# sputnik_prototype.net
KiCad netlist of a schematic drawn in EAGLE
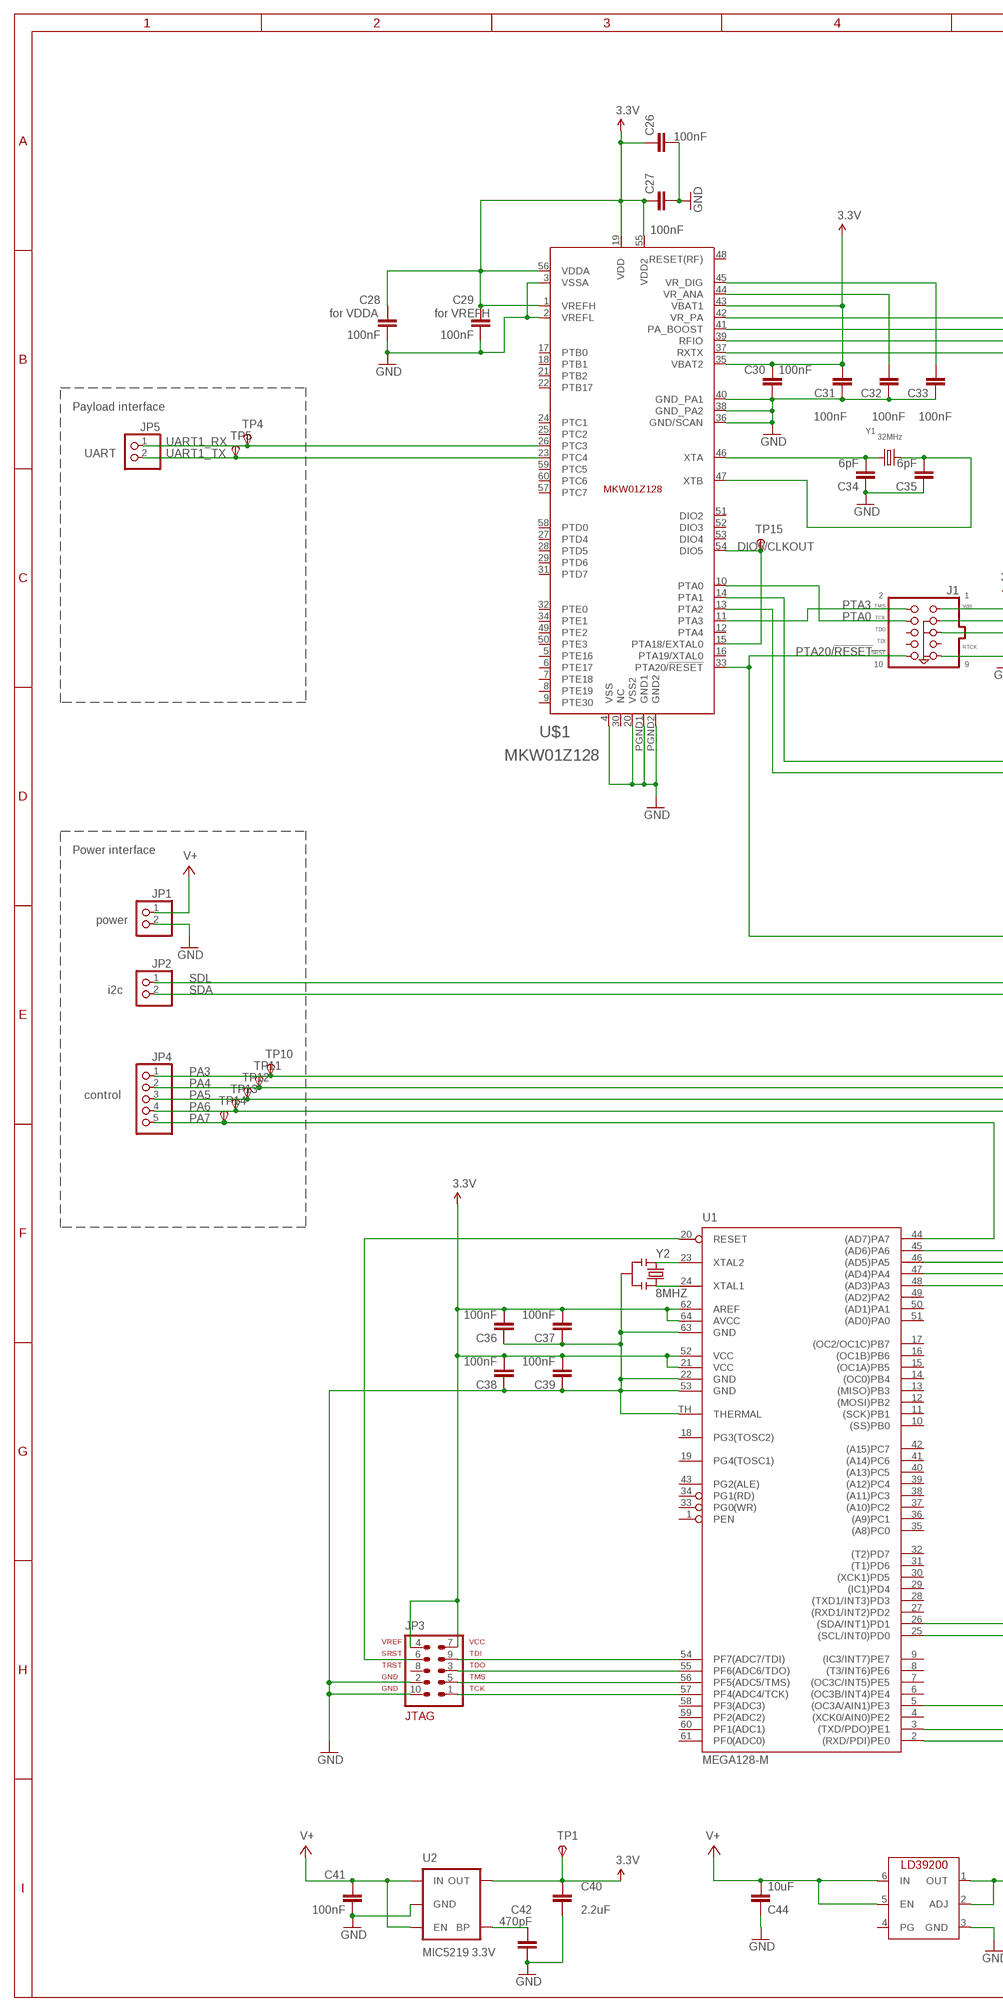
[diagram p0: schematic, sheet 1, part 1 of 2]
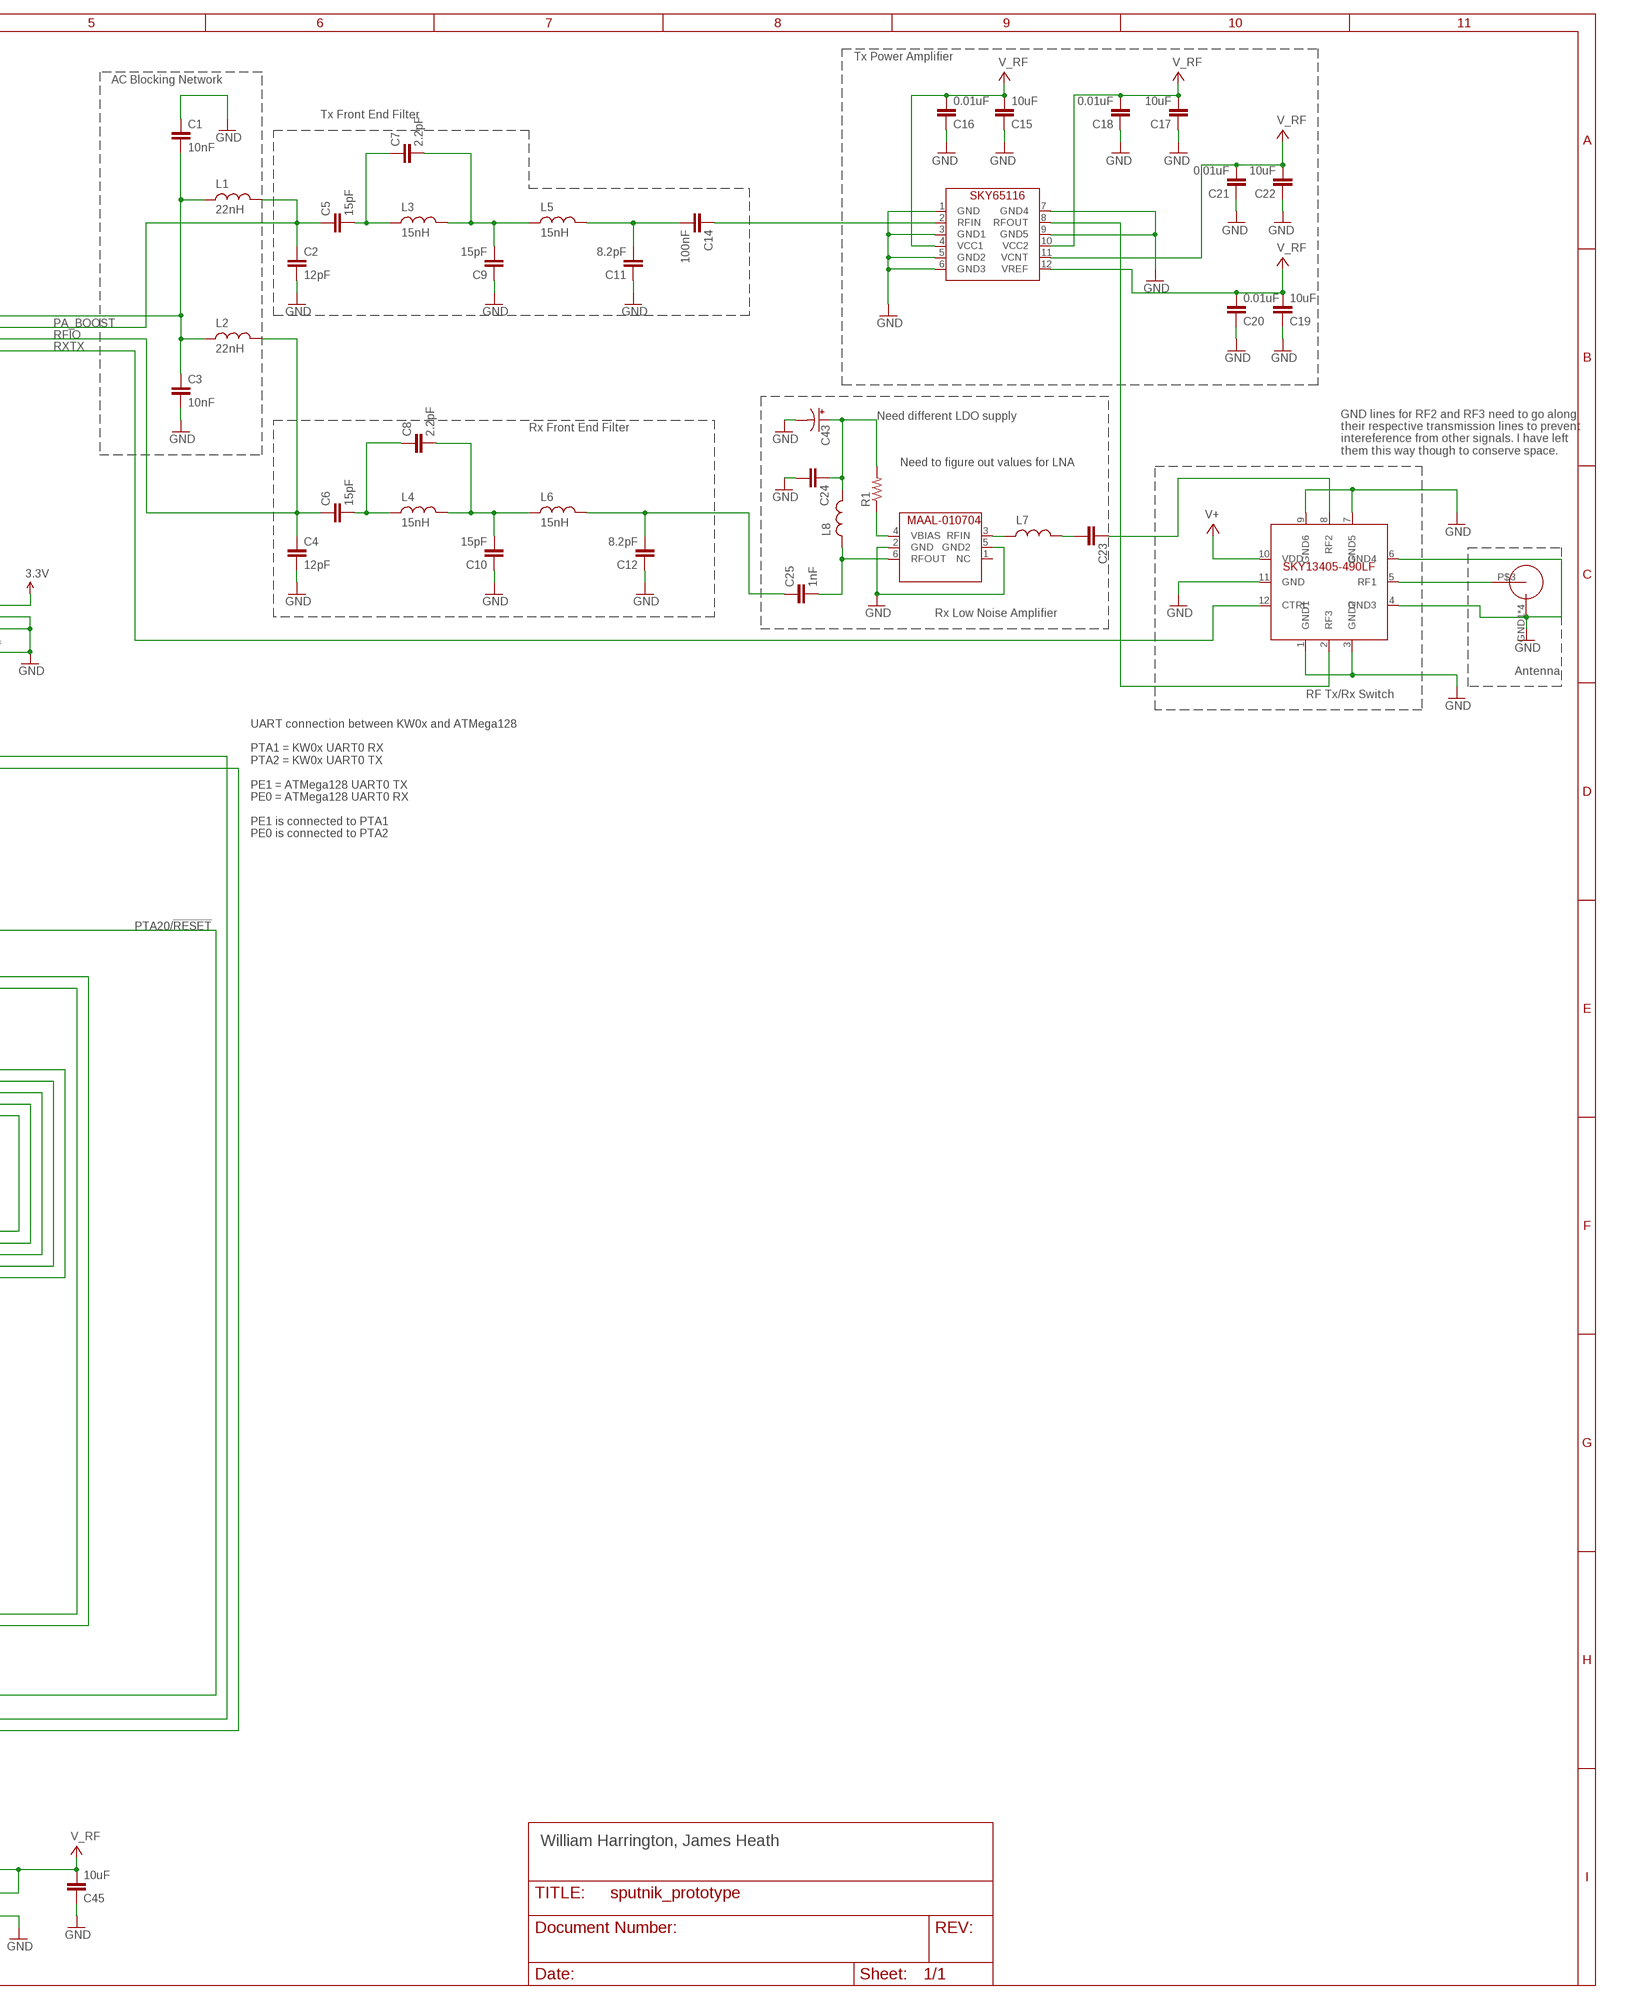
[diagram p1: schematic, sheet 1, part 2 of 2]

(export (version "E")
  (design (tool "Eeschema 10.0.6"))
  (components
    (comp (ref "C1")
      (value "10nF")
      (footprint "eagle-import:.0603-B-NOSILK")
      (libsource (lib "eagle-import") (part "C-EU0603-B-NOSILK"))
    )
    (comp (ref "C2")
      (value "12pF")
      (footprint "eagle-import:.0603-B-NOSILK")
      (libsource (lib "eagle-import") (part "C-EU0603-B-NOSILK"))
    )
    (comp (ref "C3")
      (value "10nF")
      (footprint "eagle-import:.0603-B-NOSILK")
      (libsource (lib "eagle-import") (part "C-EU0603-B-NOSILK"))
    )
    (comp (ref "C4")
      (value "12pF")
      (footprint "eagle-import:.0603-B-NOSILK")
      (libsource (lib "eagle-import") (part "C-EU0603-B-NOSILK"))
    )
    (comp (ref "C5")
      (value "15pF")
      (footprint "eagle-import:.0603-B-NOSILK")
      (libsource (lib "eagle-import") (part "C-EU0603-B-NOSILK"))
    )
    (comp (ref "C6")
      (value "15pF")
      (footprint "eagle-import:.0603-B-NOSILK")
      (libsource (lib "eagle-import") (part "C-EU0603-B-NOSILK"))
    )
    (comp (ref "C7")
      (value "2.2pF")
      (footprint "eagle-import:.0603-B-NOSILK")
      (libsource (lib "eagle-import") (part "C-EU0603-B-NOSILK"))
    )
    (comp (ref "C8")
      (value "2.2pF")
      (footprint "eagle-import:.0603-B-NOSILK")
      (libsource (lib "eagle-import") (part "C-EU0603-B-NOSILK"))
    )
    (comp (ref "C9")
      (value "15pF")
      (footprint "eagle-import:.0603-B-NOSILK")
      (libsource (lib "eagle-import") (part "C-EU0603-B-NOSILK"))
    )
    (comp (ref "C10")
      (value "15pF")
      (footprint "eagle-import:.0603-B-NOSILK")
      (libsource (lib "eagle-import") (part "C-EU0603-B-NOSILK"))
    )
    (comp (ref "C11")
      (value "8.2pF")
      (footprint "eagle-import:.0603-B-NOSILK")
      (libsource (lib "eagle-import") (part "C-EU0603-B-NOSILK"))
    )
    (comp (ref "C12")
      (value "8.2pF")
      (footprint "eagle-import:.0603-B-NOSILK")
      (libsource (lib "eagle-import") (part "C-EU0603-B-NOSILK"))
    )
    (comp (ref "C14")
      (value "100nF")
      (footprint "eagle-import:.0603-B-NOSILK")
      (libsource (lib "eagle-import") (part "C-EU0603-B-NOSILK"))
    )
    (comp (ref "C15")
      (value "10uF")
      (footprint "eagle-import:.0603-B-NOSILK")
      (libsource (lib "eagle-import") (part "C-EU0603-B-NOSILK"))
    )
    (comp (ref "C16")
      (value "0.01uF")
      (footprint "eagle-import:.0603-B-NOSILK")
      (libsource (lib "eagle-import") (part "C-EU0603-B-NOSILK"))
    )
    (comp (ref "C17")
      (value "10uF")
      (footprint "eagle-import:.0603-B-NOSILK")
      (libsource (lib "eagle-import") (part "C-EU0603-B-NOSILK"))
    )
    (comp (ref "C18")
      (value "0.01uF")
      (footprint "eagle-import:.0603-B-NOSILK")
      (libsource (lib "eagle-import") (part "C-EU0603-B-NOSILK"))
    )
    (comp (ref "C19")
      (value "10uF")
      (footprint "eagle-import:.0603-B-NOSILK")
      (libsource (lib "eagle-import") (part "C-EU0603-B-NOSILK"))
    )
    (comp (ref "C20")
      (value "0.01uF")
      (footprint "eagle-import:.0603-B-NOSILK")
      (libsource (lib "eagle-import") (part "C-EU0603-B-NOSILK"))
    )
    (comp (ref "C21")
      (value "0.01uF")
      (footprint "eagle-import:.0603-B-NOSILK")
      (libsource (lib "eagle-import") (part "C-EU0603-B-NOSILK"))
    )
    (comp (ref "C22")
      (value "10uF")
      (footprint "eagle-import:.0603-B-NOSILK")
      (libsource (lib "eagle-import") (part "C-EU0603-B-NOSILK"))
    )
    (comp (ref "C23")
      (value "C-EU0402-B-NOSILK")
      (footprint "eagle-import:.0402-B-NOSILK")
      (libsource (lib "eagle-import") (part "C-EU0402-B-NOSILK"))
    )
    (comp (ref "C24")
      (value "C-EU0402-B-NOSILK")
      (footprint "eagle-import:.0402-B-NOSILK")
      (libsource (lib "eagle-import") (part "C-EU0402-B-NOSILK"))
    )
    (comp (ref "C25")
      (value "1nF")
      (footprint "eagle-import:.0402-B-NOSILK")
      (libsource (lib "eagle-import") (part "C-EU0402-B-NOSILK"))
    )
    (comp (ref "C26")
      (value "100nF")
      (footprint "eagle-import:.0603-B-NOSILK")
      (libsource (lib "eagle-import") (part "C-EU0603-B-NOSILK"))
    )
    (comp (ref "C27")
      (value "100nF")
      (footprint "eagle-import:.0603-B-NOSILK")
      (libsource (lib "eagle-import") (part "C-EU0603-B-NOSILK"))
    )
    (comp (ref "C28")
      (value "100nF")
      (footprint "eagle-import:.0603-B-NOSILK")
      (libsource (lib "eagle-import") (part "C-EU0603-B-NOSILK"))
    )
    (comp (ref "C29")
      (value "100nF")
      (footprint "eagle-import:.0603-B-NOSILK")
      (libsource (lib "eagle-import") (part "C-EU0603-B-NOSILK"))
    )
    (comp (ref "C30")
      (value "100nF")
      (footprint "eagle-import:.0603-B-NOSILK")
      (libsource (lib "eagle-import") (part "C-EU0603-B-NOSILK"))
    )
    (comp (ref "C31")
      (value "100nF")
      (footprint "eagle-import:.0603-B-NOSILK")
      (libsource (lib "eagle-import") (part "C-EU0603-B-NOSILK"))
    )
    (comp (ref "C32")
      (value "100nF")
      (footprint "eagle-import:.0603-B-NOSILK")
      (libsource (lib "eagle-import") (part "C-EU0603-B-NOSILK"))
    )
    (comp (ref "C33")
      (value "100nF")
      (footprint "eagle-import:.0603-B-NOSILK")
      (libsource (lib "eagle-import") (part "C-EU0603-B-NOSILK"))
    )
    (comp (ref "C34")
      (value "6pF")
      (footprint "eagle-import:.0603-B-NOSILK")
      (libsource (lib "eagle-import") (part "C-EU0603-B-NOSILK"))
    )
    (comp (ref "C35")
      (value "6pF")
      (footprint "eagle-import:.0603-B-NOSILK")
      (libsource (lib "eagle-import") (part "C-EU0603-B-NOSILK"))
    )
    (comp (ref "C36")
      (value "100nF")
      (footprint "eagle-import:.0603-B-NOSILK")
      (libsource (lib "eagle-import") (part "C-EU0603-B-NOSILK"))
    )
    (comp (ref "C37")
      (value "100nF")
      (footprint "eagle-import:.0603-B-NOSILK")
      (libsource (lib "eagle-import") (part "C-EU0603-B-NOSILK"))
    )
    (comp (ref "C38")
      (value "100nF")
      (footprint "eagle-import:.0603-B-NOSILK")
      (libsource (lib "eagle-import") (part "C-EU0603-B-NOSILK"))
    )
    (comp (ref "C39")
      (value "100nF")
      (footprint "eagle-import:.0603-B-NOSILK")
      (libsource (lib "eagle-import") (part "C-EU0603-B-NOSILK"))
    )
    (comp (ref "C40")
      (value "2.2uF")
      (footprint "eagle-import:.0603-B-NOSILK")
      (libsource (lib "eagle-import") (part "C-EU0603-B-NOSILK"))
    )
    (comp (ref "C41")
      (value "100nF")
      (footprint "eagle-import:.0603-B-NOSILK")
      (libsource (lib "eagle-import") (part "C-EU0603-B-NOSILK"))
    )
    (comp (ref "C42")
      (value "470pF")
      (footprint "eagle-import:.0603-B-NOSILK")
      (libsource (lib "eagle-import") (part "C-EU0603-B-NOSILK"))
    )
    (comp (ref "C43")
      (value "CPOL-USCT6032")
      (footprint "eagle-import:CT6032")
      (libsource (lib "eagle-import") (part "CPOL-USCT6032"))
    )
    (comp (ref "C44")
      (value "10uF")
      (footprint "eagle-import:.0603-B-NOSILK")
      (libsource (lib "eagle-import") (part "C-EU0603-B-NOSILK"))
    )
    (comp (ref "C45")
      (value "10uF")
      (footprint "eagle-import:.0603-B-NOSILK")
      (libsource (lib "eagle-import") (part "C-EU0603-B-NOSILK"))
    )
    (comp (ref "J1")
      (value "JTAG_ARM-10-50MIL")
      (footprint "eagle-import:PINHEADER-2X5-0.05+POL+SILK")
      (libsource (lib "eagle-import") (part "JTAG_ARM-10-50MIL"))
    )
    (comp (ref "JP1")
      (value "PINHD-1X2")
      (footprint "eagle-import:1X02")
      (libsource (lib "eagle-import") (part "PINHD-1X2"))
    )
    (comp (ref "JP2")
      (value "PINHD-1X2")
      (footprint "eagle-import:1X02")
      (libsource (lib "eagle-import") (part "PINHD-1X2"))
    )
    (comp (ref "JP3")
      (value "AVR-JTAG-10")
      (footprint "eagle-import:AVR-JTAG-10")
      (libsource (lib "eagle-import") (part "AVR-JTAG-10"))
    )
    (comp (ref "JP4")
      (value "PINHD-1X55X2MM")
      (footprint "eagle-import:1_05X2MM")
      (libsource (lib "eagle-import") (part "PINHD-1X55X2MM"))
    )
    (comp (ref "JP5")
      (value "PINHD-1X2")
      (footprint "eagle-import:1X02")
      (libsource (lib "eagle-import") (part "PINHD-1X2"))
    )
    (comp (ref "L1")
      (value "22nH")
      (footprint "eagle-import:.0603-B-NOSILK")
      (libsource (lib "eagle-import") (part "L-US0603-B-NOSILK"))
    )
    (comp (ref "L2")
      (value "22nH")
      (footprint "eagle-import:.0603-B-NOSILK")
      (libsource (lib "eagle-import") (part "L-US0603-B-NOSILK"))
    )
    (comp (ref "L3")
      (value "15nH")
      (footprint "eagle-import:.0603-B-NOSILK")
      (libsource (lib "eagle-import") (part "L-US0603-B-NOSILK"))
    )
    (comp (ref "L4")
      (value "15nH")
      (footprint "eagle-import:.0603-B-NOSILK")
      (libsource (lib "eagle-import") (part "L-US0603-B-NOSILK"))
    )
    (comp (ref "L5")
      (value "15nH")
      (footprint "eagle-import:.0603-B-NOSILK")
      (libsource (lib "eagle-import") (part "L-US0603-B-NOSILK"))
    )
    (comp (ref "L6")
      (value "15nH")
      (footprint "eagle-import:.0603-B-NOSILK")
      (libsource (lib "eagle-import") (part "L-US0603-B-NOSILK"))
    )
    (comp (ref "L7")
      (value "L-US0402-B-NOSILK")
      (footprint "eagle-import:.0402-B-NOSILK")
      (libsource (lib "eagle-import") (part "L-US0402-B-NOSILK"))
    )
    (comp (ref "L8")
      (value "L-US0603-B-NOSILK")
      (footprint "eagle-import:.0603-B-NOSILK")
      (libsource (lib "eagle-import") (part "L-US0603-B-NOSILK"))
    )
    (comp (ref "R1")
      (value "R-US_0603-B-NOSILK")
      (footprint "eagle-import:.0603-B-NOSILK")
      (libsource (lib "eagle-import") (part "R-US_0603-B-NOSILK"))
    )
    (comp (ref "TP1")
      (value "TPSPAD1-13")
      (footprint "eagle-import:P1-13")
      (libsource (lib "eagle-import") (part "TPSPAD1-13"))
    )
    (comp (ref "TP4")
      (value "TPSPAD1-13")
      (footprint "eagle-import:P1-13")
      (libsource (lib "eagle-import") (part "TPSPAD1-13"))
    )
    (comp (ref "TP5")
      (value "TPSPAD1-13")
      (footprint "eagle-import:P1-13")
      (libsource (lib "eagle-import") (part "TPSPAD1-13"))
    )
    (comp (ref "TP10")
      (value "TPSPAD1-13")
      (footprint "eagle-import:P1-13")
      (libsource (lib "eagle-import") (part "TPSPAD1-13"))
    )
    (comp (ref "TP11")
      (value "TPSPAD1-13")
      (footprint "eagle-import:P1-13")
      (libsource (lib "eagle-import") (part "TPSPAD1-13"))
    )
    (comp (ref "TP12")
      (value "TPSPAD1-13")
      (footprint "eagle-import:P1-13")
      (libsource (lib "eagle-import") (part "TPSPAD1-13"))
    )
    (comp (ref "TP13")
      (value "TPSPAD1-13")
      (footprint "eagle-import:P1-13")
      (libsource (lib "eagle-import") (part "TPSPAD1-13"))
    )
    (comp (ref "TP14")
      (value "TPSPAD1-13")
      (footprint "eagle-import:P1-13")
      (libsource (lib "eagle-import") (part "TPSPAD1-13"))
    )
    (comp (ref "TP15")
      (value "TPSPAD1-13")
      (footprint "eagle-import:P1-13")
      (libsource (lib "eagle-import") (part "TPSPAD1-13"))
    )
    (comp (ref "U$1")
      (value "MKW01Z128")
      (footprint "eagle-import:MKW01Z128")
      (libsource (lib "eagle-import") (part "MKW01Z128"))
    )
    (comp (ref "U$2")
      (value "SMAJ716-ND")
      (footprint "eagle-import:SMAJ716-ND")
      (libsource (lib "eagle-import") (part "SMAJ716-ND"))
    )
    (comp (ref "U$3")
      (value "LD39200")
      (footprint "eagle-import:LD39200")
      (libsource (lib "eagle-import") (part "LD39200"))
    )
    (comp (ref "U$4")
      (value "MAAL-010704")
      (footprint "eagle-import:MAAL-010704")
      (libsource (lib "eagle-import") (part "MAAL-010704"))
    )
    (comp (ref "U$5")
      (value "SKY13405-490LF")
      (footprint "eagle-import:SKY13405-490LF")
      (libsource (lib "eagle-import") (part "SKY13405-490LF"))
    )
    (comp (ref "U$6")
      (value "SKY65116")
      (footprint "eagle-import:SKY65116")
      (libsource (lib "eagle-import") (part "SKY65116"))
    )
    (comp (ref "U1")
      (value "MEGA128-M")
      (footprint "eagle-import:MLF64-TH")
      (fields (field (name "MPN") "ATMEGA128-16MU"))
      (libsource (lib "eagle-import") (part "MEGA128-M"))
    )
    (comp (ref "U2")
      (value "MIC5219 3.3V")
      (footprint "eagle-import:SPARKFUN-POWERIC_SOT23-5")
      (libsource (lib "eagle-import") (part "SPARKFUN-POWERIC_V_REG_MIC52193.3V"))
    )
    (comp (ref "Y1")
      (value "32MHz")
      (footprint "eagle-import:CRYSTAL_2.5X2")
      (fields (field (name "MFG") "EPSON") (field (name "MPN") "FA20H 32.0000MF12Y-W3"))
      (libsource (lib "eagle-import") (part "CRYSTAL2.5X2.0MM"))
    )
    (comp (ref "Y2")
      (value "8MHZ")
      (footprint "eagle-import:SPARKFUN-FREQCTRL_RESONATOR-SMD")
      (libsource (lib "eagle-import") (part "SPARKFUN-FREQCTRL_RESONATOR8MHZ"))
    )
  )
  (nets
    (net (code "1") (name "/DIO5{slash}CLKOUT") (class "Default")
      (node (ref "TP15") (pin "TP") (pinfunction "PP_TP") (pintype "input"))
      (node (ref "U$1") (pin "15") (pinfunction "PTA18/EXTAL0_15") (pintype "bidirectional"))
      (node (ref "U$1") (pin "54") (pinfunction "DIO5_54") (pintype "bidirectional"))
    )
    (net (code "2") (name "/PA3") (class "Default")
      (node (ref "JP4") (pin "1") (pinfunction "1_1") (pintype "passive"))
      (node (ref "TP10") (pin "TP") (pinfunction "PP_TP") (pintype "input"))
      (node (ref "U1") (pin "48") (pinfunction "(AD3)PA3_48") (pintype "bidirectional"))
    )
    (net (code "3") (name "/PA4") (class "Default")
      (node (ref "JP4") (pin "2") (pinfunction "2_2") (pintype "passive"))
      (node (ref "TP11") (pin "TP") (pinfunction "PP_TP") (pintype "input"))
      (node (ref "U1") (pin "47") (pinfunction "(AD4)PA4_47") (pintype "bidirectional"))
    )
    (net (code "4") (name "/PA5") (class "Default")
      (node (ref "JP4") (pin "3") (pinfunction "3_3") (pintype "passive"))
      (node (ref "TP12") (pin "TP") (pinfunction "PP_TP") (pintype "input"))
      (node (ref "U1") (pin "46") (pinfunction "(AD5)PA5_46") (pintype "bidirectional"))
    )
    (net (code "5") (name "/PA6") (class "Default")
      (node (ref "JP4") (pin "4") (pinfunction "4_4") (pintype "passive"))
      (node (ref "TP13") (pin "TP") (pinfunction "PP_TP") (pintype "input"))
      (node (ref "U1") (pin "45") (pinfunction "(AD6)PA6_45") (pintype "bidirectional"))
    )
    (net (code "6") (name "/PA7") (class "Default")
      (node (ref "JP4") (pin "5") (pinfunction "5_5") (pintype "passive"))
      (node (ref "TP14") (pin "TP") (pinfunction "PP_TP") (pintype "input"))
      (node (ref "U1") (pin "44") (pinfunction "(AD7)PA7_44") (pintype "bidirectional"))
    )
    (net (code "7") (name "/PA_BOOST") (class "Default")
      (node (ref "C2") (pin "1") (pinfunction "1_1") (pintype "passive"))
      (node (ref "C5") (pin "1") (pinfunction "1_1") (pintype "passive"))
      (node (ref "L1") (pin "2") (pinfunction "2_2") (pintype "passive"))
      (node (ref "U$1") (pin "41") (pinfunction "PA_BOOST_41") (pintype "output"))
    )
    (net (code "8") (name "/PTA0") (class "Default")
      (node (ref "J1") (pin "4") (pinfunction "TCK_4") (pintype "passive"))
      (node (ref "U$1") (pin "10") (pinfunction "PTA0_10") (pintype "bidirectional"))
    )
    (net (code "9") (name "/PTA3") (class "Default")
      (node (ref "J1") (pin "2") (pinfunction "TMS_2") (pintype "passive"))
      (node (ref "U$1") (pin "11") (pinfunction "PTA3_11") (pintype "bidirectional"))
    )
    (net (code "10") (name "/PTA20{slash}~{RESET}") (class "Default")
      (node (ref "J1") (pin "10") (pinfunction "SRST_10") (pintype "passive"))
      (node (ref "U$1") (pin "33") (pinfunction "PTA20/~{RESET}_33") (pintype "bidirectional"))
      (node (ref "U1") (pin "5") (pinfunction "(OC3A/AIN1)PE3_5") (pintype "bidirectional"))
    )
    (net (code "11") (name "/RFIO") (class "Default")
      (node (ref "C4") (pin "1") (pinfunction "1_1") (pintype "passive"))
      (node (ref "C6") (pin "1") (pinfunction "1_1") (pintype "passive"))
      (node (ref "L2") (pin "2") (pinfunction "2_2") (pintype "passive"))
      (node (ref "U$1") (pin "39") (pinfunction "RFIO_39") (pintype "bidirectional"))
    )
    (net (code "12") (name "/RXTX") (class "Default")
      (node (ref "U$1") (pin "37") (pinfunction "RXTX_37") (pintype "output"))
      (node (ref "U$5") (pin "12") (pinfunction "CTRL_12") (pintype "input"))
    )
    (net (code "13") (name "/SDA") (class "Default")
      (node (ref "JP2") (pin "2") (pinfunction "2_2") (pintype "passive"))
      (node (ref "U1") (pin "26") (pinfunction "(SDA/INT1)PD1_26") (pintype "bidirectional"))
    )
    (net (code "14") (name "/SDL") (class "Default")
      (node (ref "JP2") (pin "1") (pinfunction "1_1") (pintype "passive"))
      (node (ref "U1") (pin "25") (pinfunction "(SCL/INT0)PD0_25") (pintype "bidirectional"))
    )
    (net (code "15") (name "/UART1_RX") (class "Default")
      (node (ref "JP5") (pin "1") (pinfunction "1_1") (pintype "passive"))
      (node (ref "TP4") (pin "TP") (pinfunction "PP_TP") (pintype "input"))
      (node (ref "U$1") (pin "26") (pinfunction "PTC3_26") (pintype "bidirectional"))
    )
    (net (code "16") (name "/UART1_TX") (class "Default")
      (node (ref "JP5") (pin "2") (pinfunction "2_2") (pintype "passive"))
      (node (ref "TP5") (pin "TP") (pinfunction "PP_TP") (pintype "input"))
      (node (ref "U$1") (pin "23") (pinfunction "PTC4_23") (pintype "bidirectional"))
    )
    (net (code "17") (name "3.3V") (class "Default")
      (node (ref "C26") (pin "1") (pinfunction "1_1") (pintype "passive"))
      (node (ref "C27") (pin "1") (pinfunction "1_1") (pintype "passive"))
      (node (ref "C28") (pin "2") (pinfunction "2_2") (pintype "passive"))
      (node (ref "C29") (pin "2") (pinfunction "2_2") (pintype "passive"))
      (node (ref "C30") (pin "2") (pinfunction "2_2") (pintype "passive"))
      (node (ref "C31") (pin "2") (pinfunction "2_2") (pintype "passive"))
      (node (ref "C36") (pin "2") (pinfunction "2_2") (pintype "passive"))
      (node (ref "C37") (pin "2") (pinfunction "2_2") (pintype "passive"))
      (node (ref "C38") (pin "2") (pinfunction "2_2") (pintype "passive"))
      (node (ref "C39") (pin "2") (pinfunction "2_2") (pintype "passive"))
      (node (ref "C40") (pin "2") (pinfunction "2_2") (pintype "passive"))
      (node (ref "J1") (pin "1") (pinfunction "VDD_1") (pintype "passive"))
      (node (ref "JP3") (pin "4") (pinfunction "4_4") (pintype "passive"))
      (node (ref "JP3") (pin "7") (pinfunction "7_7") (pintype "passive"))
      (node (ref "TP1") (pin "TP") (pinfunction "PP_TP") (pintype "input"))
      (node (ref "U$1") (pin "1") (pinfunction "VREFH_1") (pintype "input"))
      (node (ref "U$1") (pin "19") (pinfunction "VDD_19") (pintype "power_in"))
      (node (ref "U$1") (pin "35") (pinfunction "VBAT2_35") (pintype "power_in"))
      (node (ref "U$1") (pin "43") (pinfunction "VBAT1_43") (pintype "power_in"))
      (node (ref "U$1") (pin "55") (pinfunction "VDD2_55") (pintype "power_in"))
      (node (ref "U$1") (pin "56") (pinfunction "VDDA_56") (pintype "power_in"))
      (node (ref "U1") (pin "21") (pinfunction "VCC_21") (pintype "power_in"))
      (node (ref "U1") (pin "52") (pinfunction "VCC_52") (pintype "power_in"))
      (node (ref "U1") (pin "62") (pinfunction "AREF_62") (pintype "passive"))
      (node (ref "U1") (pin "64") (pinfunction "AVCC_64") (pintype "power_in"))
      (node (ref "U2") (pin "5") (pinfunction "OUT_5") (pintype "passive"))
    )
    (net (code "18") (name "GND") (class "Default")
      (node (ref "C1") (pin "1") (pinfunction "1_1") (pintype "passive"))
      (node (ref "C10") (pin "1") (pinfunction "1_1") (pintype "passive"))
      (node (ref "C11") (pin "1") (pinfunction "1_1") (pintype "passive"))
      (node (ref "C12") (pin "1") (pinfunction "1_1") (pintype "passive"))
      (node (ref "C15") (pin "1") (pinfunction "1_1") (pintype "passive"))
      (node (ref "C16") (pin "1") (pinfunction "1_1") (pintype "passive"))
      (node (ref "C17") (pin "1") (pinfunction "1_1") (pintype "passive"))
      (node (ref "C18") (pin "1") (pinfunction "1_1") (pintype "passive"))
      (node (ref "C19") (pin "1") (pinfunction "1_1") (pintype "passive"))
      (node (ref "C2") (pin "2") (pinfunction "2_2") (pintype "passive"))
      (node (ref "C20") (pin "1") (pinfunction "1_1") (pintype "passive"))
      (node (ref "C21") (pin "1") (pinfunction "1_1") (pintype "passive"))
      (node (ref "C22") (pin "1") (pinfunction "1_1") (pintype "passive"))
      (node (ref "C24") (pin "2") (pinfunction "2_2") (pintype "passive"))
      (node (ref "C26") (pin "2") (pinfunction "2_2") (pintype "passive"))
      (node (ref "C27") (pin "2") (pinfunction "2_2") (pintype "passive"))
      (node (ref "C28") (pin "1") (pinfunction "1_1") (pintype "passive"))
      (node (ref "C29") (pin "1") (pinfunction "1_1") (pintype "passive"))
      (node (ref "C3") (pin "2") (pinfunction "2_2") (pintype "passive"))
      (node (ref "C30") (pin "1") (pinfunction "1_1") (pintype "passive"))
      (node (ref "C31") (pin "1") (pinfunction "1_1") (pintype "passive"))
      (node (ref "C32") (pin "1") (pinfunction "1_1") (pintype "passive"))
      (node (ref "C33") (pin "1") (pinfunction "1_1") (pintype "passive"))
      (node (ref "C34") (pin "1") (pinfunction "1_1") (pintype "passive"))
      (node (ref "C35") (pin "1") (pinfunction "1_1") (pintype "passive"))
      (node (ref "C36") (pin "1") (pinfunction "1_1") (pintype "passive"))
      (node (ref "C37") (pin "1") (pinfunction "1_1") (pintype "passive"))
      (node (ref "C38") (pin "1") (pinfunction "1_1") (pintype "passive"))
      (node (ref "C39") (pin "1") (pinfunction "1_1") (pintype "passive"))
      (node (ref "C4") (pin "2") (pinfunction "2_2") (pintype "passive"))
      (node (ref "C40") (pin "1") (pinfunction "1_1") (pintype "passive"))
      (node (ref "C41") (pin "1") (pinfunction "1_1") (pintype "passive"))
      (node (ref "C42") (pin "1") (pinfunction "1_1") (pintype "passive"))
      (node (ref "C43") (pin "-") (pinfunction "-_-") (pintype "passive"))
      (node (ref "C44") (pin "1") (pinfunction "1_1") (pintype "passive"))
      (node (ref "C45") (pin "1") (pinfunction "1_1") (pintype "passive"))
      (node (ref "C9") (pin "1") (pinfunction "1_1") (pintype "passive"))
      (node (ref "J1") (pin "3") (pinfunction "GND3_3") (pintype "passive"))
      (node (ref "J1") (pin "5") (pinfunction "GND5_5") (pintype "passive"))
      (node (ref "J1") (pin "9") (pinfunction "GND9_9") (pintype "passive"))
      (node (ref "JP1") (pin "2") (pinfunction "2_2") (pintype "passive"))
      (node (ref "JP3") (pin "10") (pinfunction "10_10") (pintype "passive"))
      (node (ref "JP3") (pin "2") (pinfunction "2_2") (pintype "passive"))
      (node (ref "U$1") (pin "2") (pinfunction "VREFL_2") (pintype "input"))
      (node (ref "U$1") (pin "20") (pinfunction "VSS2_20") (pintype "power_in"))
      (node (ref "U$1") (pin "3") (pinfunction "VSSA_3") (pintype "power_in"))
      (node (ref "U$1") (pin "36") (pinfunction "GND/SCAN_36") (pintype "power_in"))
      (node (ref "U$1") (pin "38") (pinfunction "GND_PA2_38") (pintype "power_in"))
      (node (ref "U$1") (pin "4") (pinfunction "VSS_4") (pintype "power_in"))
      (node (ref "U$1") (pin "40") (pinfunction "GND_PA1_40") (pintype "power_in"))
      (node (ref "U$1") (pin "PGND1") (pinfunction "GND1_PGND1") (pintype "power_in"))
      (node (ref "U$1") (pin "PGND2") (pinfunction "GND2_PGND2") (pintype "power_in"))
      (node (ref "U$2") (pin "GND1") (pinfunction "OUTERCONDUCTOR_GND1") (pintype "bidirectional"))
      (node (ref "U$2") (pin "GND2") (pinfunction "OUTERCONDUCTOR_GND2") (pintype "bidirectional"))
      (node (ref "U$2") (pin "GND3") (pinfunction "OUTERCONDUCTOR_GND3") (pintype "bidirectional"))
      (node (ref "U$2") (pin "GND4") (pinfunction "OUTERCONDUCTOR_GND4") (pintype "bidirectional"))
      (node (ref "U$3") (pin "3") (pinfunction "GND_3") (pintype "bidirectional"))
      (node (ref "U$4") (pin "2") (pinfunction "GND_2") (pintype "bidirectional"))
      (node (ref "U$4") (pin "5") (pinfunction "GND2_5") (pintype "bidirectional"))
      (node (ref "U$5") (pin "1") (pinfunction "GND1_1") (pintype "bidirectional"))
      (node (ref "U$5") (pin "11") (pinfunction "GND_11") (pintype "bidirectional"))
      (node (ref "U$5") (pin "3") (pinfunction "GND2_3") (pintype "bidirectional"))
      (node (ref "U$5") (pin "4") (pinfunction "GND3_4") (pintype "bidirectional"))
      (node (ref "U$5") (pin "6") (pinfunction "GND4_6") (pintype "bidirectional"))
      (node (ref "U$5") (pin "7") (pinfunction "GND5_7") (pintype "bidirectional"))
      (node (ref "U$5") (pin "9") (pinfunction "GND6_9") (pintype "bidirectional"))
      (node (ref "U$6") (pin "1") (pinfunction "GND_1") (pintype "bidirectional"))
      (node (ref "U$6") (pin "3") (pinfunction "GND1_3") (pintype "bidirectional"))
      (node (ref "U$6") (pin "5") (pinfunction "GND2_5") (pintype "bidirectional"))
      (node (ref "U$6") (pin "6") (pinfunction "GND3_6") (pintype "bidirectional"))
      (node (ref "U$6") (pin "7") (pinfunction "GND4_7") (pintype "bidirectional"))
      (node (ref "U$6") (pin "9") (pinfunction "GND5_9") (pintype "bidirectional"))
      (node (ref "U1") (pin "22") (pinfunction "GND_22") (pintype "power_in"))
      (node (ref "U1") (pin "53") (pinfunction "GND_53") (pintype "power_in"))
      (node (ref "U1") (pin "63") (pinfunction "GND_63") (pintype "power_in"))
      (node (ref "U1") (pin "TH") (pinfunction "THERMAL_TH") (pintype "input"))
      (node (ref "U2") (pin "2") (pinfunction "GND_2") (pintype "input"))
      (node (ref "Y2") (pin "2") (pinfunction "2_2") (pintype "passive"))
    )
    (net (code "19") (name "Net-(C5-Pad2)") (class "Default")
      (node (ref "C5") (pin "2") (pinfunction "2_2") (pintype "passive"))
      (node (ref "C7") (pin "1") (pinfunction "1_1") (pintype "passive"))
      (node (ref "L3") (pin "1") (pinfunction "1_1") (pintype "passive"))
    )
    (net (code "20") (name "Net-(C6-Pad2)") (class "Default")
      (node (ref "C6") (pin "2") (pinfunction "2_2") (pintype "passive"))
      (node (ref "C8") (pin "1") (pinfunction "1_1") (pintype "passive"))
      (node (ref "L4") (pin "1") (pinfunction "1_1") (pintype "passive"))
    )
    (net (code "21") (name "Net-(C7-Pad2)") (class "Default")
      (node (ref "C7") (pin "2") (pinfunction "2_2") (pintype "passive"))
      (node (ref "C9") (pin "2") (pinfunction "2_2") (pintype "passive"))
      (node (ref "L3") (pin "2") (pinfunction "2_2") (pintype "passive"))
      (node (ref "L5") (pin "1") (pinfunction "1_1") (pintype "passive"))
    )
    (net (code "22") (name "Net-(C10-Pad2)") (class "Default")
      (node (ref "C10") (pin "2") (pinfunction "2_2") (pintype "passive"))
      (node (ref "C8") (pin "2") (pinfunction "2_2") (pintype "passive"))
      (node (ref "L4") (pin "2") (pinfunction "2_2") (pintype "passive"))
      (node (ref "L6") (pin "1") (pinfunction "1_1") (pintype "passive"))
    )
    (net (code "23") (name "Net-(C11-Pad2)") (class "Default")
      (node (ref "C11") (pin "2") (pinfunction "2_2") (pintype "passive"))
      (node (ref "C14") (pin "2") (pinfunction "2_2") (pintype "passive"))
      (node (ref "L5") (pin "2") (pinfunction "2_2") (pintype "passive"))
    )
    (net (code "24") (name "Net-(C12-Pad2)") (class "Default")
      (node (ref "C12") (pin "2") (pinfunction "2_2") (pintype "passive"))
      (node (ref "C25") (pin "1") (pinfunction "1_1") (pintype "passive"))
      (node (ref "L6") (pin "2") (pinfunction "2_2") (pintype "passive"))
    )
    (net (code "25") (name "Net-(C23-Pad2)") (class "Default")
      (node (ref "C23") (pin "2") (pinfunction "2_2") (pintype "passive"))
      (node (ref "L7") (pin "2") (pinfunction "2_2") (pintype "passive"))
    )
    (net (code "26") (name "Net-(C24-Pad1)") (class "Default")
      (node (ref "C24") (pin "1") (pinfunction "1_1") (pintype "passive"))
      (node (ref "C43") (pin "+") (pinfunction "+_+") (pintype "passive"))
      (node (ref "L8") (pin "2") (pinfunction "2_2") (pintype "passive"))
      (node (ref "R1") (pin "2") (pinfunction "2_2") (pintype "passive"))
    )
    (net (code "27") (name "Net-(U$1-PTA1)") (class "Default")
      (node (ref "U$1") (pin "14") (pinfunction "PTA1_14") (pintype "bidirectional"))
      (node (ref "U1") (pin "3") (pinfunction "(TXD/PDO)PE1_3") (pintype "bidirectional"))
    )
    (net (code "28") (name "Net-(U$1-PTA2)") (class "Default")
      (node (ref "U$1") (pin "13") (pinfunction "PTA2_13") (pintype "bidirectional"))
      (node (ref "U1") (pin "2") (pinfunction "(RXD/PDI)PE0_2") (pintype "bidirectional"))
    )
    (net (code "29") (name "Net-(U$1-VR_ANA)") (class "Default")
      (node (ref "C32") (pin "2") (pinfunction "2_2") (pintype "passive"))
      (node (ref "U$1") (pin "44") (pinfunction "VR_ANA_44") (pintype "output"))
    )
    (net (code "30") (name "Net-(U$1-VR_DIG)") (class "Default")
      (node (ref "C33") (pin "2") (pinfunction "2_2") (pintype "passive"))
      (node (ref "U$1") (pin "45") (pinfunction "VR_DIG_45") (pintype "output"))
    )
    (net (code "31") (name "Net-(U$1-VR_PA)") (class "Default")
      (node (ref "C1") (pin "2") (pinfunction "2_2") (pintype "passive"))
      (node (ref "C3") (pin "1") (pinfunction "1_1") (pintype "passive"))
      (node (ref "L1") (pin "1") (pinfunction "1_1") (pintype "passive"))
      (node (ref "L2") (pin "1") (pinfunction "1_1") (pintype "passive"))
      (node (ref "U$1") (pin "42") (pinfunction "VR_PA_42") (pintype "output"))
    )
    (net (code "32") (name "Net-(U$1-XTA)") (class "Default")
      (node (ref "C34") (pin "2") (pinfunction "2_2") (pintype "passive"))
      (node (ref "U$1") (pin "46") (pinfunction "XTA_46") (pintype "passive"))
      (node (ref "Y1") (pin "1") (pinfunction "1_1") (pintype "passive"))
    )
    (net (code "33") (name "Net-(U$1-XTB)") (class "Default")
      (node (ref "C35") (pin "2") (pinfunction "2_2") (pintype "passive"))
      (node (ref "U$1") (pin "47") (pinfunction "XTB_47") (pintype "passive"))
      (node (ref "Y1") (pin "3") (pinfunction "2_3") (pintype "passive"))
    )
    (net (code "34") (name "Net-(U$2-CENTERCONDUCTOR)") (class "Default")
      (node (ref "U$2") (pin "P$3") (pinfunction "CENTERCONDUCTOR_P$3") (pintype "bidirectional"))
      (node (ref "U$5") (pin "5") (pinfunction "RF1_5") (pintype "bidirectional"))
    )
    (net (code "35") (name "Net-(U$4-RFIN)") (class "Default")
      (node (ref "L7") (pin "1") (pinfunction "1_1") (pintype "passive"))
      (node (ref "U$4") (pin "3") (pinfunction "RFIN_3") (pintype "input"))
    )
    (net (code "36") (name "Net-(U$4-RFOUT)") (class "Default")
      (node (ref "C25") (pin "2") (pinfunction "2_2") (pintype "passive"))
      (node (ref "L8") (pin "1") (pinfunction "1_1") (pintype "passive"))
      (node (ref "U$4") (pin "6") (pinfunction "RFOUT_6") (pintype "output"))
    )
    (net (code "37") (name "Net-(U$4-VBIAS)") (class "Default")
      (node (ref "R1") (pin "1") (pinfunction "1_1") (pintype "passive"))
      (node (ref "U$4") (pin "4") (pinfunction "VBIAS_4") (pintype "power_in"))
    )
    (net (code "38") (name "Net-(U$5-RF2)") (class "Default")
      (node (ref "C23") (pin "1") (pinfunction "1_1") (pintype "passive"))
      (node (ref "U$5") (pin "8") (pinfunction "RF2_8") (pintype "bidirectional"))
    )
    (net (code "39") (name "Net-(U$5-RF3)") (class "Default")
      (node (ref "U$5") (pin "2") (pinfunction "RF3_2") (pintype "bidirectional"))
      (node (ref "U$6") (pin "8") (pinfunction "RFOUT_8") (pintype "output"))
    )
    (net (code "40") (name "Net-(U$6-RFIN)") (class "Default")
      (node (ref "C14") (pin "1") (pinfunction "1_1") (pintype "passive"))
      (node (ref "U$6") (pin "2") (pinfunction "RFIN_2") (pintype "input"))
    )
    (net (code "41") (name "Net-(U1-PF4(ADC4{slash}TCK))") (class "Default")
      (node (ref "JP3") (pin "1") (pinfunction "1_1") (pintype "passive"))
      (node (ref "U1") (pin "57") (pinfunction "PF4(ADC4/TCK)_57") (pintype "input"))
    )
    (net (code "42") (name "Net-(U1-PF5(ADC5{slash}TMS))") (class "Default")
      (node (ref "JP3") (pin "5") (pinfunction "5_5") (pintype "passive"))
      (node (ref "U1") (pin "56") (pinfunction "PF5(ADC5/TMS)_56") (pintype "input"))
    )
    (net (code "43") (name "Net-(U1-PF6(ADC6{slash}TDO))") (class "Default")
      (node (ref "JP3") (pin "3") (pinfunction "3_3") (pintype "passive"))
      (node (ref "U1") (pin "55") (pinfunction "PF6(ADC6/TDO)_55") (pintype "input"))
    )
    (net (code "44") (name "Net-(U1-PF7(ADC7{slash}TDI))") (class "Default")
      (node (ref "JP3") (pin "9") (pinfunction "9_9") (pintype "passive"))
      (node (ref "U1") (pin "54") (pinfunction "PF7(ADC7/TDI)_54") (pintype "input"))
    )
    (net (code "45") (name "Net-(U1-RESET)") (class "Default")
      (node (ref "JP3") (pin "6") (pinfunction "6_6") (pintype "passive"))
      (node (ref "U1") (pin "20") (pinfunction "RESET_20") (pintype "input"))
    )
    (net (code "46") (name "Net-(U1-XTAL1)") (class "Default")
      (node (ref "U1") (pin "24") (pinfunction "XTAL1_24") (pintype "bidirectional"))
      (node (ref "Y2") (pin "3") (pinfunction "3_3") (pintype "passive"))
    )
    (net (code "47") (name "Net-(U1-XTAL2)") (class "Default")
      (node (ref "U1") (pin "23") (pinfunction "XTAL2_23") (pintype "bidirectional"))
      (node (ref "Y2") (pin "1") (pinfunction "1_1") (pintype "passive"))
    )
    (net (code "48") (name "Net-(U2-BP)") (class "Default")
      (node (ref "C42") (pin "2") (pinfunction "2_2") (pintype "passive"))
      (node (ref "U2") (pin "4") (pinfunction "BP_4") (pintype "input"))
    )
    (net (code "49") (name "V+") (class "Default")
      (node (ref "C15") (pin "2") (pinfunction "2_2") (pintype "passive"))
      (node (ref "C16") (pin "2") (pinfunction "2_2") (pintype "passive"))
      (node (ref "C17") (pin "2") (pinfunction "2_2") (pintype "passive"))
      (node (ref "C18") (pin "2") (pinfunction "2_2") (pintype "passive"))
      (node (ref "C19") (pin "2") (pinfunction "2_2") (pintype "passive"))
      (node (ref "C20") (pin "2") (pinfunction "2_2") (pintype "passive"))
      (node (ref "C21") (pin "2") (pinfunction "2_2") (pintype "passive"))
      (node (ref "C22") (pin "2") (pinfunction "2_2") (pintype "passive"))
      (node (ref "C41") (pin "2") (pinfunction "2_2") (pintype "passive"))
      (node (ref "C44") (pin "2") (pinfunction "2_2") (pintype "passive"))
      (node (ref "C45") (pin "2") (pinfunction "2_2") (pintype "passive"))
      (node (ref "JP1") (pin "1") (pinfunction "1_1") (pintype "passive"))
      (node (ref "U$3") (pin "1") (pinfunction "OUT_1") (pintype "output"))
      (node (ref "U$3") (pin "2") (pinfunction "ADJ_2") (pintype "bidirectional"))
      (node (ref "U$3") (pin "5") (pinfunction "EN_5") (pintype "bidirectional"))
      (node (ref "U$3") (pin "6") (pinfunction "IN_6") (pintype "input"))
      (node (ref "U$5") (pin "10") (pinfunction "VDD_10") (pintype "power_in"))
      (node (ref "U$6") (pin "10") (pinfunction "VCC2_10") (pintype "power_in"))
      (node (ref "U$6") (pin "11") (pinfunction "VCNT_11") (pintype "power_in"))
      (node (ref "U$6") (pin "12") (pinfunction "VREF_12") (pintype "power_in"))
      (node (ref "U$6") (pin "4") (pinfunction "VCC1_4") (pintype "power_in"))
      (node (ref "U2") (pin "1") (pinfunction "IN_1") (pintype "input"))
      (node (ref "U2") (pin "3") (pinfunction "EN_3") (pintype "input"))
    )
    (net (code "50") (name "unconnected-(J1-RTCK-Pad7)") (class "Default")
      (node (ref "J1") (pin "7") (pinfunction "RTCK_7") (pintype "passive"))
    )
    (net (code "51") (name "unconnected-(J1-TDI-Pad8)") (class "Default")
      (node (ref "J1") (pin "8") (pinfunction "TDI_8") (pintype "passive"))
    )
    (net (code "52") (name "unconnected-(J1-TDO-Pad6)") (class "Default")
      (node (ref "J1") (pin "6") (pinfunction "TDO_6") (pintype "passive"))
    )
    (net (code "53") (name "unconnected-(JP3-Pad8)") (class "Default")
      (node (ref "JP3") (pin "8") (pinfunction "8_8") (pintype "passive"))
    )
    (net (code "54") (name "unconnected-(U$1-DIO2-Pad51)") (class "Default")
      (node (ref "U$1") (pin "51") (pinfunction "DIO2_51") (pintype "bidirectional"))
    )
    (net (code "55") (name "unconnected-(U$1-DIO3-Pad52)") (class "Default")
      (node (ref "U$1") (pin "52") (pinfunction "DIO3_52") (pintype "bidirectional"))
    )
    (net (code "56") (name "unconnected-(U$1-DIO4-Pad53)") (class "Default")
      (node (ref "U$1") (pin "53") (pinfunction "DIO4_53") (pintype "bidirectional"))
    )
    (net (code "57") (name "unconnected-(U$1-NC-Pad30)") (class "Default")
      (node (ref "U$1") (pin "30") (pinfunction "NC_30") (pintype "no_connect"))
    )
    (net (code "58") (name "unconnected-(U$1-PTA4-Pad12)") (class "Default")
      (node (ref "U$1") (pin "12") (pinfunction "PTA4_12") (pintype "bidirectional"))
    )
    (net (code "59") (name "unconnected-(U$1-PTA19{slash}XTAL0-Pad16)") (class "Default")
      (node (ref "U$1") (pin "16") (pinfunction "PTA19/XTAL0_16") (pintype "bidirectional"))
    )
    (net (code "60") (name "unconnected-(U$1-PTB0-Pad17)") (class "Default")
      (node (ref "U$1") (pin "17") (pinfunction "PTB0_17") (pintype "bidirectional"))
    )
    (net (code "61") (name "unconnected-(U$1-PTB1-Pad18)") (class "Default")
      (node (ref "U$1") (pin "18") (pinfunction "PTB1_18") (pintype "bidirectional"))
    )
    (net (code "62") (name "unconnected-(U$1-PTB2-Pad21)") (class "Default")
      (node (ref "U$1") (pin "21") (pinfunction "PTB2_21") (pintype "bidirectional"))
    )
    (net (code "63") (name "unconnected-(U$1-PTB17-Pad22)") (class "Default")
      (node (ref "U$1") (pin "22") (pinfunction "PTB17_22") (pintype "bidirectional"))
    )
    (net (code "64") (name "unconnected-(U$1-PTC1-Pad24)") (class "Default")
      (node (ref "U$1") (pin "24") (pinfunction "PTC1_24") (pintype "bidirectional"))
    )
    (net (code "65") (name "unconnected-(U$1-PTC2-Pad25)") (class "Default")
      (node (ref "U$1") (pin "25") (pinfunction "PTC2_25") (pintype "bidirectional"))
    )
    (net (code "66") (name "unconnected-(U$1-PTC5-Pad59)") (class "Default")
      (node (ref "U$1") (pin "59") (pinfunction "PTC5_59") (pintype "bidirectional"))
    )
    (net (code "67") (name "unconnected-(U$1-PTC6-Pad60)") (class "Default")
      (node (ref "U$1") (pin "60") (pinfunction "PTC6_60") (pintype "bidirectional"))
    )
    (net (code "68") (name "unconnected-(U$1-PTC7-Pad57)") (class "Default")
      (node (ref "U$1") (pin "57") (pinfunction "PTC7_57") (pintype "bidirectional"))
    )
    (net (code "69") (name "unconnected-(U$1-PTD0-Pad58)") (class "Default")
      (node (ref "U$1") (pin "58") (pinfunction "PTD0_58") (pintype "bidirectional"))
    )
    (net (code "70") (name "unconnected-(U$1-PTD4-Pad27)") (class "Default")
      (node (ref "U$1") (pin "27") (pinfunction "PTD4_27") (pintype "bidirectional"))
    )
    (net (code "71") (name "unconnected-(U$1-PTD5-Pad28)") (class "Default")
      (node (ref "U$1") (pin "28") (pinfunction "PTD5_28") (pintype "bidirectional"))
    )
    (net (code "72") (name "unconnected-(U$1-PTD6-Pad29)") (class "Default")
      (node (ref "U$1") (pin "29") (pinfunction "PTD6_29") (pintype "bidirectional"))
    )
    (net (code "73") (name "unconnected-(U$1-PTD7-Pad31)") (class "Default")
      (node (ref "U$1") (pin "31") (pinfunction "PTD7_31") (pintype "bidirectional"))
    )
    (net (code "74") (name "unconnected-(U$1-PTE0-Pad32)") (class "Default")
      (node (ref "U$1") (pin "32") (pinfunction "PTE0_32") (pintype "bidirectional"))
    )
    (net (code "75") (name "unconnected-(U$1-PTE1-Pad34)") (class "Default")
      (node (ref "U$1") (pin "34") (pinfunction "PTE1_34") (pintype "bidirectional"))
    )
    (net (code "76") (name "unconnected-(U$1-PTE2-Pad49)") (class "Default")
      (node (ref "U$1") (pin "49") (pinfunction "PTE2_49") (pintype "bidirectional"))
    )
    (net (code "77") (name "unconnected-(U$1-PTE3-Pad50)") (class "Default")
      (node (ref "U$1") (pin "50") (pinfunction "PTE3_50") (pintype "bidirectional"))
    )
    (net (code "78") (name "unconnected-(U$1-PTE16-Pad5)") (class "Default")
      (node (ref "U$1") (pin "5") (pinfunction "PTE16_5") (pintype "bidirectional"))
    )
    (net (code "79") (name "unconnected-(U$1-PTE17-Pad6)") (class "Default")
      (node (ref "U$1") (pin "6") (pinfunction "PTE17_6") (pintype "bidirectional"))
    )
    (net (code "80") (name "unconnected-(U$1-PTE18-Pad7)") (class "Default")
      (node (ref "U$1") (pin "7") (pinfunction "PTE18_7") (pintype "bidirectional"))
    )
    (net (code "81") (name "unconnected-(U$1-PTE19-Pad8)") (class "Default")
      (node (ref "U$1") (pin "8") (pinfunction "PTE19_8") (pintype "bidirectional"))
    )
    (net (code "82") (name "unconnected-(U$1-PTE30-Pad9)") (class "Default")
      (node (ref "U$1") (pin "9") (pinfunction "PTE30_9") (pintype "bidirectional"))
    )
    (net (code "83") (name "unconnected-(U$1-RESET(RF)-Pad48)") (class "Default")
      (node (ref "U$1") (pin "48") (pinfunction "RESET(RF)_48") (pintype "input"))
    )
    (net (code "84") (name "unconnected-(U$3-PG-Pad4)") (class "Default")
      (node (ref "U$3") (pin "4") (pinfunction "PG_4") (pintype "bidirectional"))
    )
    (net (code "85") (name "unconnected-(U$4-NC-Pad1)") (class "Default")
      (node (ref "U$4") (pin "1") (pinfunction "NC_1") (pintype "bidirectional"))
    )
    (net (code "86") (name "unconnected-(U1-(A8)PC0-Pad35)") (class "Default")
      (node (ref "U1") (pin "35") (pinfunction "(A8)PC0_35") (pintype "output"))
    )
    (net (code "87") (name "unconnected-(U1-(A9)PC1-Pad36)") (class "Default")
      (node (ref "U1") (pin "36") (pinfunction "(A9)PC1_36") (pintype "output"))
    )
    (net (code "88") (name "unconnected-(U1-(A10)PC2-Pad37)") (class "Default")
      (node (ref "U1") (pin "37") (pinfunction "(A10)PC2_37") (pintype "output"))
    )
    (net (code "89") (name "unconnected-(U1-(A11)PC3-Pad38)") (class "Default")
      (node (ref "U1") (pin "38") (pinfunction "(A11)PC3_38") (pintype "output"))
    )
    (net (code "90") (name "unconnected-(U1-(A12)PC4-Pad39)") (class "Default")
      (node (ref "U1") (pin "39") (pinfunction "(A12)PC4_39") (pintype "output"))
    )
    (net (code "91") (name "unconnected-(U1-(A13)PC5-Pad40)") (class "Default")
      (node (ref "U1") (pin "40") (pinfunction "(A13)PC5_40") (pintype "output"))
    )
    (net (code "92") (name "unconnected-(U1-(A14)PC6-Pad41)") (class "Default")
      (node (ref "U1") (pin "41") (pinfunction "(A14)PC6_41") (pintype "output"))
    )
    (net (code "93") (name "unconnected-(U1-(A15)PC7-Pad42)") (class "Default")
      (node (ref "U1") (pin "42") (pinfunction "(A15)PC7_42") (pintype "output"))
    )
    (net (code "94") (name "unconnected-(U1-(AD0)PA0-Pad51)") (class "Default")
      (node (ref "U1") (pin "51") (pinfunction "(AD0)PA0_51") (pintype "bidirectional"))
    )
    (net (code "95") (name "unconnected-(U1-(AD1)PA1-Pad50)") (class "Default")
      (node (ref "U1") (pin "50") (pinfunction "(AD1)PA1_50") (pintype "bidirectional"))
    )
    (net (code "96") (name "unconnected-(U1-(AD2)PA2-Pad49)") (class "Default")
      (node (ref "U1") (pin "49") (pinfunction "(AD2)PA2_49") (pintype "bidirectional"))
    )
    (net (code "97") (name "unconnected-(U1-(IC1)PD4-Pad29)") (class "Default")
      (node (ref "U1") (pin "29") (pinfunction "(IC1)PD4_29") (pintype "bidirectional"))
    )
    (net (code "98") (name "unconnected-(U1-(IC3{slash}INT7)PE7-Pad9)") (class "Default")
      (node (ref "U1") (pin "9") (pinfunction "(IC3/INT7)PE7_9") (pintype "bidirectional"))
    )
    (net (code "99") (name "unconnected-(U1-(MISO)PB3-Pad13)") (class "Default")
      (node (ref "U1") (pin "13") (pinfunction "(MISO)PB3_13") (pintype "bidirectional"))
    )
    (net (code "100") (name "unconnected-(U1-(MOSI)PB2-Pad12)") (class "Default")
      (node (ref "U1") (pin "12") (pinfunction "(MOSI)PB2_12") (pintype "bidirectional"))
    )
    (net (code "101") (name "unconnected-(U1-(OC0)PB4-Pad14)") (class "Default")
      (node (ref "U1") (pin "14") (pinfunction "(OC0)PB4_14") (pintype "bidirectional"))
    )
    (net (code "102") (name "unconnected-(U1-(OC1A)PB5-Pad15)") (class "Default")
      (node (ref "U1") (pin "15") (pinfunction "(OC1A)PB5_15") (pintype "bidirectional"))
    )
    (net (code "103") (name "unconnected-(U1-(OC1B)PB6-Pad16)") (class "Default")
      (node (ref "U1") (pin "16") (pinfunction "(OC1B)PB6_16") (pintype "bidirectional"))
    )
    (net (code "104") (name "unconnected-(U1-(OC2{slash}OC1C)PB7-Pad17)") (class "Default")
      (node (ref "U1") (pin "17") (pinfunction "(OC2/OC1C)PB7_17") (pintype "bidirectional"))
    )
    (net (code "105") (name "unconnected-(U1-(OC3B{slash}INT4)PE4-Pad6)") (class "Default")
      (node (ref "U1") (pin "6") (pinfunction "(OC3B/INT4)PE4_6") (pintype "bidirectional"))
    )
    (net (code "106") (name "unconnected-(U1-(OC3C{slash}INT5)PE5-Pad7)") (class "Default")
      (node (ref "U1") (pin "7") (pinfunction "(OC3C/INT5)PE5_7") (pintype "bidirectional"))
    )
    (net (code "107") (name "unconnected-(U1-(RXD1{slash}INT2)PD2-Pad27)") (class "Default")
      (node (ref "U1") (pin "27") (pinfunction "(RXD1/INT2)PD2_27") (pintype "bidirectional"))
    )
    (net (code "108") (name "unconnected-(U1-(SCK)PB1-Pad11)") (class "Default")
      (node (ref "U1") (pin "11") (pinfunction "(SCK)PB1_11") (pintype "bidirectional"))
    )
    (net (code "109") (name "unconnected-(U1-(SS)PB0-Pad10)") (class "Default")
      (node (ref "U1") (pin "10") (pinfunction "(SS)PB0_10") (pintype "bidirectional"))
    )
    (net (code "110") (name "unconnected-(U1-(T1)PD6-Pad31)") (class "Default")
      (node (ref "U1") (pin "31") (pinfunction "(T1)PD6_31") (pintype "bidirectional"))
    )
    (net (code "111") (name "unconnected-(U1-(T2)PD7-Pad32)") (class "Default")
      (node (ref "U1") (pin "32") (pinfunction "(T2)PD7_32") (pintype "bidirectional"))
    )
    (net (code "112") (name "unconnected-(U1-(T3{slash}INT6)PE6-Pad8)") (class "Default")
      (node (ref "U1") (pin "8") (pinfunction "(T3/INT6)PE6_8") (pintype "bidirectional"))
    )
    (net (code "113") (name "unconnected-(U1-(TXD1{slash}INT3)PD3-Pad28)") (class "Default")
      (node (ref "U1") (pin "28") (pinfunction "(TXD1/INT3)PD3_28") (pintype "bidirectional"))
    )
    (net (code "114") (name "unconnected-(U1-(XCK0{slash}AIN0)PE2-Pad4)") (class "Default")
      (node (ref "U1") (pin "4") (pinfunction "(XCK0/AIN0)PE2_4") (pintype "bidirectional"))
    )
    (net (code "115") (name "unconnected-(U1-(XCK1)PD5-Pad30)") (class "Default")
      (node (ref "U1") (pin "30") (pinfunction "(XCK1)PD5_30") (pintype "bidirectional"))
    )
    (net (code "116") (name "unconnected-(U1-PEN-Pad1)") (class "Default")
      (node (ref "U1") (pin "1") (pinfunction "PEN_1") (pintype "input"))
    )
    (net (code "117") (name "unconnected-(U1-PF0(ADC0)-Pad61)") (class "Default")
      (node (ref "U1") (pin "61") (pinfunction "PF0(ADC0)_61") (pintype "input"))
    )
    (net (code "118") (name "unconnected-(U1-PF1(ADC1)-Pad60)") (class "Default")
      (node (ref "U1") (pin "60") (pinfunction "PF1(ADC1)_60") (pintype "input"))
    )
    (net (code "119") (name "unconnected-(U1-PF2(ADC2)-Pad59)") (class "Default")
      (node (ref "U1") (pin "59") (pinfunction "PF2(ADC2)_59") (pintype "input"))
    )
    (net (code "120") (name "unconnected-(U1-PF3(ADC3)-Pad58)") (class "Default")
      (node (ref "U1") (pin "58") (pinfunction "PF3(ADC3)_58") (pintype "input"))
    )
    (net (code "121") (name "unconnected-(U1-PG0(WR)-Pad33)") (class "Default")
      (node (ref "U1") (pin "33") (pinfunction "PG0(WR)_33") (pintype "bidirectional"))
    )
    (net (code "122") (name "unconnected-(U1-PG1(RD)-Pad34)") (class "Default")
      (node (ref "U1") (pin "34") (pinfunction "PG1(RD)_34") (pintype "bidirectional"))
    )
    (net (code "123") (name "unconnected-(U1-PG2(ALE)-Pad43)") (class "Default")
      (node (ref "U1") (pin "43") (pinfunction "PG2(ALE)_43") (pintype "bidirectional"))
    )
    (net (code "124") (name "unconnected-(U1-PG3(TOSC2)-Pad18)") (class "Default")
      (node (ref "U1") (pin "18") (pinfunction "PG3(TOSC2)_18") (pintype "bidirectional"))
    )
    (net (code "125") (name "unconnected-(U1-PG4(TOSC1)-Pad19)") (class "Default")
      (node (ref "U1") (pin "19") (pinfunction "PG4(TOSC1)_19") (pintype "bidirectional"))
    )
  )
)
